# 532_Encoder.net
KiCad netlist of a schematic drawn in Altium Designer
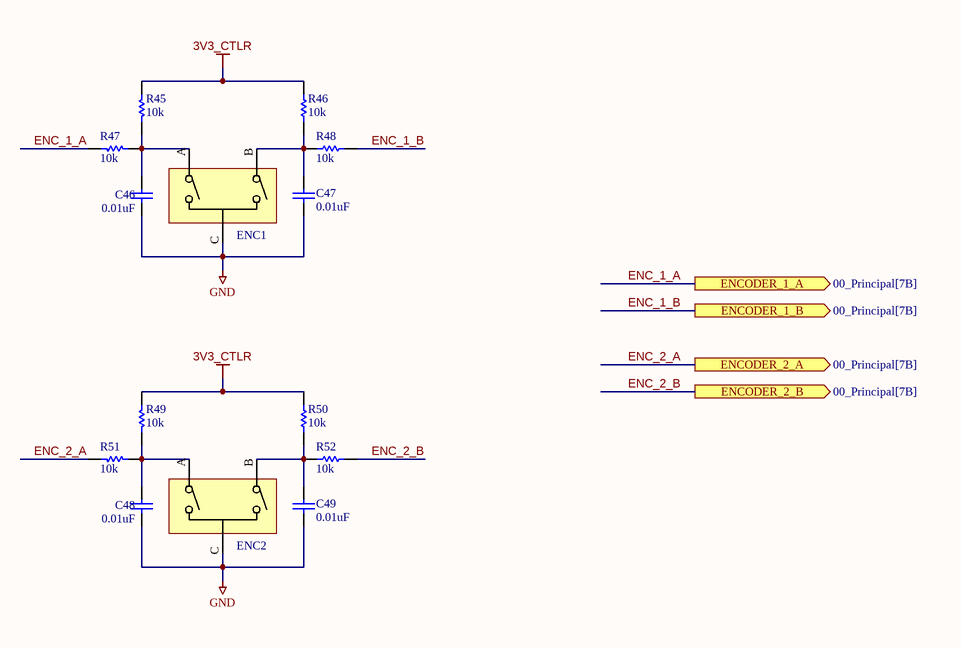
[diagram p0: 532_Encoder.SchDoc]

(export (version "E")
  (design (tool "Eeschema 10.0.6"))
  (components
    (comp (ref "C46")
      (value "0.01uF")
      (footprint "CAPC1005X55X25LL05T10")
      (fields (field (name "MANUFACTURER") "Murata") (field (name "PART NUMBER") "GRM155R71E103KA01D"))
      (libsource (lib "Altium Content Vault") (part "CAP"))
    )
    (comp (ref "C47")
      (value "0.01uF")
      (footprint "CAPC1005X55X25LL05T10")
      (fields (field (name "MANUFACTURER") "Murata") (field (name "PART NUMBER") "GRM155R71E103KA01D"))
      (libsource (lib "Altium Content Vault") (part "CAP"))
    )
    (comp (ref "C48")
      (value "0.01uF")
      (footprint "CAPC1005X55X25LL05T10")
      (fields (field (name "MANUFACTURER") "Murata") (field (name "PART NUMBER") "GRM155R71E103KA01D"))
      (libsource (lib "Altium Content Vault") (part "CAP"))
    )
    (comp (ref "C49")
      (value "0.01uF")
      (footprint "CAPC1005X55X25LL05T10")
      (fields (field (name "MANUFACTURER") "Murata") (field (name "PART NUMBER") "GRM155R71E103KA01D"))
      (libsource (lib "Altium Content Vault") (part "CAP"))
    )
    (comp (ref "ENC1")
      (value "Encoder")
      (footprint "PEC09-2315F-N0015")
      (description "PEC09 PC Pin Quadrature (Incremental) 12 Mechanical Encoder 11.4mm 70C")
      (fields
        (field (name "MANUFACTURER") "Bourns")
        (field (name "MANUFACTURER PART NUMBER") "PEC09-2315F-N0015")
      )
      (libsource (lib "Esquemas") (part "PEC09-2315F-N0015"))
    )
    (comp (ref "ENC2")
      (value "Encoder")
      (footprint "PEC09-2315F-N0015")
      (description "PEC09 PC Pin Quadrature (Incremental) 12 Mechanical Encoder 11.4mm 70C")
      (fields
        (field (name "MANUFACTURER") "Bourns")
        (field (name "MANUFACTURER PART NUMBER") "PEC09-2315F-N0015")
      )
      (libsource (lib "Esquemas") (part "PEC09-2315F-N0015"))
    )
    (comp (ref "R45")
      (value "10k")
      (footprint "RESC1005X40X25ML05T05")
      (fields (field (name "MANUFACTURER") "Panasonic") (field (name "PART NUMBER") "ERJ-2RHD1002X"))
      (libsource (lib "Altium Content Vault") (part "RES"))
    )
    (comp (ref "R46")
      (value "10k")
      (footprint "RESC1005X40X25ML05T05")
      (fields (field (name "MANUFACTURER") "Panasonic") (field (name "PART NUMBER") "ERJ-2RHD1002X"))
      (libsource (lib "Altium Content Vault") (part "RES"))
    )
    (comp (ref "R47")
      (value "10k")
      (footprint "RESC1005X40X25ML05T05")
      (fields (field (name "MANUFACTURER") "Panasonic") (field (name "PART NUMBER") "ERJ-2RHD1002X"))
      (libsource (lib "Altium Content Vault") (part "RES"))
    )
    (comp (ref "R48")
      (value "10k")
      (footprint "RESC1005X40X25ML05T05")
      (fields (field (name "MANUFACTURER") "Panasonic") (field (name "PART NUMBER") "ERJ-2RHD1002X"))
      (libsource (lib "Altium Content Vault") (part "RES"))
    )
    (comp (ref "R49")
      (value "10k")
      (footprint "RESC1005X40X25ML05T05")
      (fields (field (name "MANUFACTURER") "Panasonic") (field (name "PART NUMBER") "ERJ-2RHD1002X"))
      (libsource (lib "Altium Content Vault") (part "RES"))
    )
    (comp (ref "R50")
      (value "10k")
      (footprint "RESC1005X40X25ML05T05")
      (fields (field (name "MANUFACTURER") "Panasonic") (field (name "PART NUMBER") "ERJ-2RHD1002X"))
      (libsource (lib "Altium Content Vault") (part "RES"))
    )
    (comp (ref "R51")
      (value "10k")
      (footprint "RESC1005X40X25ML05T05")
      (fields (field (name "MANUFACTURER") "Panasonic") (field (name "PART NUMBER") "ERJ-2RHD1002X"))
      (libsource (lib "Altium Content Vault") (part "RES"))
    )
    (comp (ref "R52")
      (value "10k")
      (footprint "RESC1005X40X25ML05T05")
      (fields (field (name "MANUFACTURER") "Panasonic") (field (name "PART NUMBER") "ERJ-2RHD1002X"))
      (libsource (lib "Altium Content Vault") (part "RES"))
    )
  )
  (nets
    (net (code "1") (name "/ENC_1_A") (class "Default")
      (node (ref "R47") (pin "1") (pinfunction "1_1") (pintype "passive"))
    )
    (net (code "2") (name "/ENC_1_B") (class "Default")
      (node (ref "R48") (pin "1") (pinfunction "1_1") (pintype "passive"))
    )
    (net (code "3") (name "/ENC_2_A") (class "Default")
      (node (ref "R51") (pin "1") (pinfunction "1_1") (pintype "passive"))
    )
    (net (code "4") (name "/ENC_2_B") (class "Default")
      (node (ref "R52") (pin "1") (pinfunction "1_1") (pintype "passive"))
    )
    (net (code "5") (name "3V3_CTLR") (class "Default")
      (node (ref "R45") (pin "1") (pinfunction "1_1") (pintype "passive"))
      (node (ref "R46") (pin "1") (pinfunction "1_1") (pintype "passive"))
      (node (ref "R49") (pin "1") (pinfunction "1_1") (pintype "passive"))
      (node (ref "R50") (pin "1") (pinfunction "1_1") (pintype "passive"))
    )
    (net (code "6") (name "GND") (class "Default")
      (node (ref "C46") (pin "1") (pinfunction "1_1") (pintype "passive"))
      (node (ref "C47") (pin "1") (pinfunction "1_1") (pintype "passive"))
      (node (ref "C48") (pin "1") (pinfunction "1_1") (pintype "passive"))
      (node (ref "C49") (pin "1") (pinfunction "1_1") (pintype "passive"))
      (node (ref "ENC1") (pin "C") (pinfunction "COM_C") (pintype "passive"))
      (node (ref "ENC2") (pin "C") (pinfunction "COM_C") (pintype "passive"))
    )
    (net (code "7") (name "Net-(C46-Pad2)") (class "Default")
      (node (ref "C46") (pin "2") (pinfunction "2_2") (pintype "passive"))
      (node (ref "ENC1") (pin "A") (pinfunction "COM_A") (pintype "passive"))
      (node (ref "R45") (pin "2") (pinfunction "2_2") (pintype "passive"))
      (node (ref "R47") (pin "2") (pinfunction "2_2") (pintype "passive"))
    )
    (net (code "8") (name "Net-(C47-Pad2)") (class "Default")
      (node (ref "C47") (pin "2") (pinfunction "2_2") (pintype "passive"))
      (node (ref "ENC1") (pin "B") (pinfunction "COM_B") (pintype "passive"))
      (node (ref "R46") (pin "2") (pinfunction "2_2") (pintype "passive"))
      (node (ref "R48") (pin "2") (pinfunction "2_2") (pintype "passive"))
    )
    (net (code "9") (name "Net-(C48-Pad2)") (class "Default")
      (node (ref "C48") (pin "2") (pinfunction "2_2") (pintype "passive"))
      (node (ref "ENC2") (pin "A") (pinfunction "COM_A") (pintype "passive"))
      (node (ref "R49") (pin "2") (pinfunction "2_2") (pintype "passive"))
      (node (ref "R51") (pin "2") (pinfunction "2_2") (pintype "passive"))
    )
    (net (code "10") (name "Net-(C49-Pad2)") (class "Default")
      (node (ref "C49") (pin "2") (pinfunction "2_2") (pintype "passive"))
      (node (ref "ENC2") (pin "B") (pinfunction "COM_B") (pintype "passive"))
      (node (ref "R50") (pin "2") (pinfunction "2_2") (pintype "passive"))
      (node (ref "R52") (pin "2") (pinfunction "2_2") (pintype "passive"))
    )
  )
)
